# murdock_conn_v2.net
KiCad netlist of a schematic drawn in EAGLE
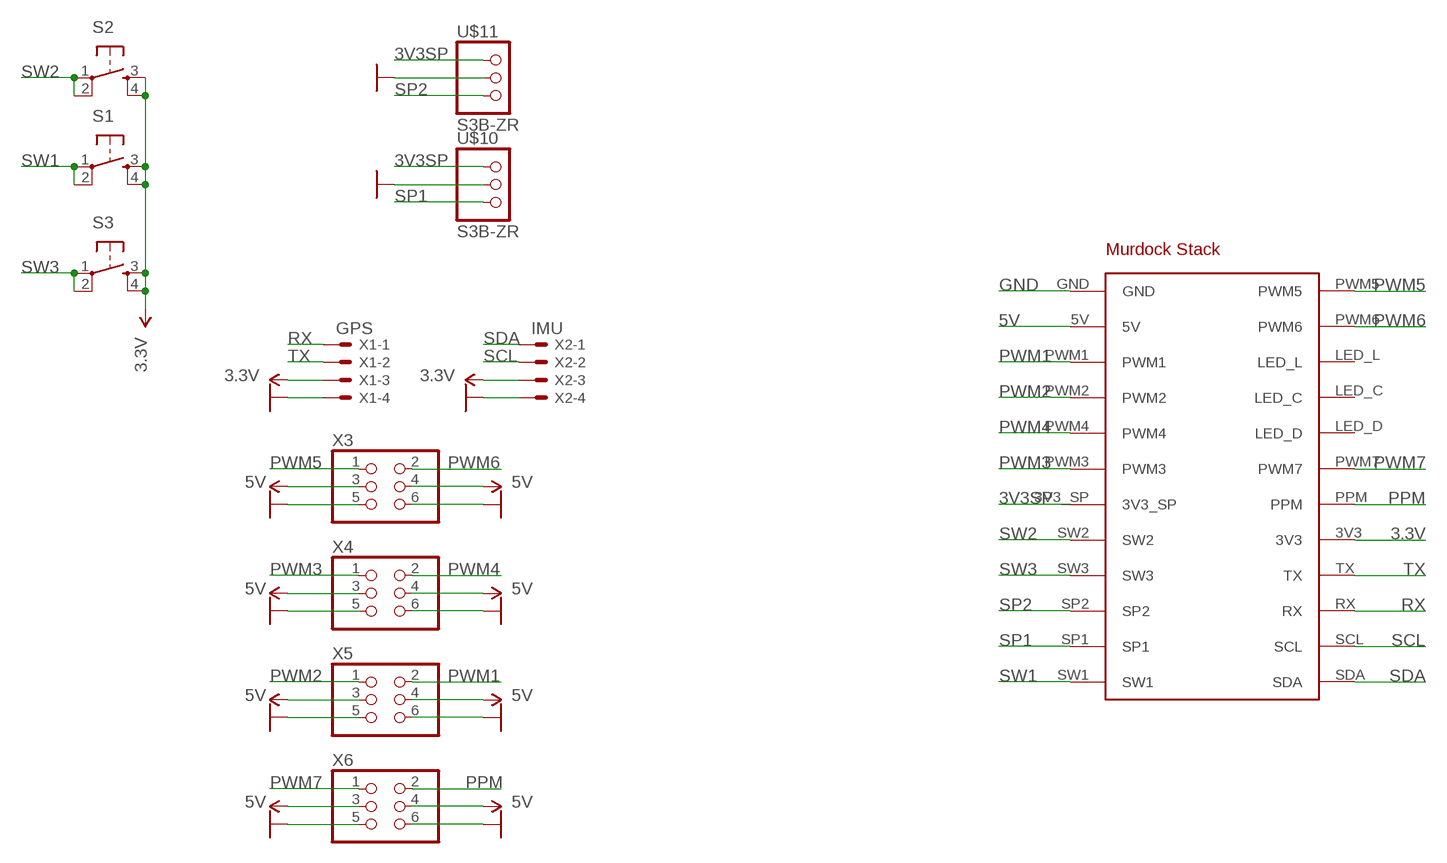
[diagram p0: schematic, sheet 1]

(export (version "E")
  (design (tool "Eeschema 10.0.6"))
  (components
    (comp (ref "S1")
      (value "LSH")
      (footprint "eagle-import:LSH")
      (libsource (lib "eagle-import") (part "LSH"))
    )
    (comp (ref "S2")
      (value "LSH")
      (footprint "eagle-import:LSH")
      (libsource (lib "eagle-import") (part "LSH"))
    )
    (comp (ref "S3")
      (value "LSH")
      (footprint "eagle-import:LSH")
      (libsource (lib "eagle-import") (part "LSH"))
    )
    (comp (ref "U$10")
      (value "S3B-ZR")
      (footprint "eagle-import:S3B-ZR")
      (libsource (lib "eagle-import") (part "S3B-ZR"))
    )
    (comp (ref "U$11")
      (value "S3B-ZR")
      (footprint "eagle-import:S3B-ZR")
      (libsource (lib "eagle-import") (part "S3B-ZR"))
    )
    (comp (ref "X1")
      (value "GPS")
      (footprint "eagle-import:70553-04")
      (libsource (lib "eagle-import") (part "C-GRID-04-70553"))
    )
    (comp (ref "X2")
      (value "IMU")
      (footprint "eagle-import:70553-04")
      (libsource (lib "eagle-import") (part "C-GRID-04-70553"))
    )
    (comp (ref "X3")
      (value "PINHD-2X3/90")
      (footprint "eagle-import:2X03_90")
      (libsource (lib "eagle-import") (part "PINHD-2X3/90"))
    )
    (comp (ref "X4")
      (value "PINHD-2X3/90")
      (footprint "eagle-import:2X03_90")
      (libsource (lib "eagle-import") (part "PINHD-2X3/90"))
    )
    (comp (ref "X5")
      (value "PINHD-2X3/90")
      (footprint "eagle-import:2X03_90")
      (libsource (lib "eagle-import") (part "PINHD-2X3/90"))
    )
    (comp (ref "X6")
      (value "PINHD-2X3/90")
      (footprint "eagle-import:2X03_90")
      (libsource (lib "eagle-import") (part "PINHD-2X3/90"))
    )
    (comp (ref "X7")
      (value "MURDOCK_STACK")
      (footprint "eagle-import:MURDOCK_STACK")
      (libsource (lib "eagle-import") (part "MURDOCK_STACK"))
    )
  )
  (nets
    (net (code "1") (name "/3V3SP") (class "Default")
      (node (ref "U$10") (pin "1") (pinfunction "1_1") (pintype "bidirectional"))
      (node (ref "U$11") (pin "1") (pinfunction "1_1") (pintype "bidirectional"))
      (node (ref "X7") (pin "3V3_SP") (pinfunction "3V3_SP_3V3_SP") (pintype "bidirectional"))
    )
    (net (code "2") (name "/PPM") (class "Default")
      (node (ref "X6") (pin "2") (pinfunction "2_2") (pintype "passive"))
      (node (ref "X7") (pin "PPM") (pinfunction "PPM_PPM") (pintype "bidirectional"))
    )
    (net (code "3") (name "/PWM1") (class "Default")
      (node (ref "X5") (pin "2") (pinfunction "2_2") (pintype "passive"))
      (node (ref "X7") (pin "PWM1") (pinfunction "PWM1_PWM1") (pintype "bidirectional"))
    )
    (net (code "4") (name "/PWM2") (class "Default")
      (node (ref "X5") (pin "1") (pinfunction "1_1") (pintype "passive"))
      (node (ref "X7") (pin "PWM2") (pinfunction "PWM2_PWM2") (pintype "bidirectional"))
    )
    (net (code "5") (name "/PWM3") (class "Default")
      (node (ref "X4") (pin "1") (pinfunction "1_1") (pintype "passive"))
      (node (ref "X7") (pin "PWM3") (pinfunction "PWM3_PWM3") (pintype "bidirectional"))
    )
    (net (code "6") (name "/PWM4") (class "Default")
      (node (ref "X4") (pin "2") (pinfunction "2_2") (pintype "passive"))
      (node (ref "X7") (pin "PWM4") (pinfunction "PWM4_PWM4") (pintype "bidirectional"))
    )
    (net (code "7") (name "/PWM5") (class "Default")
      (node (ref "X3") (pin "1") (pinfunction "1_1") (pintype "passive"))
      (node (ref "X7") (pin "PWM5") (pinfunction "PWM5_PWM5") (pintype "bidirectional"))
    )
    (net (code "8") (name "/PWM6") (class "Default")
      (node (ref "X3") (pin "2") (pinfunction "2_2") (pintype "passive"))
      (node (ref "X7") (pin "PWM6") (pinfunction "PWM6_PWM6") (pintype "bidirectional"))
    )
    (net (code "9") (name "/PWM7") (class "Default")
      (node (ref "X6") (pin "1") (pinfunction "1_1") (pintype "passive"))
      (node (ref "X7") (pin "PWM7") (pinfunction "PWM7_PWM7") (pintype "bidirectional"))
    )
    (net (code "10") (name "/RX") (class "Default")
      (node (ref "X1") (pin "1") (pinfunction "S_1") (pintype "passive"))
      (node (ref "X7") (pin "RX") (pinfunction "RX_RX") (pintype "bidirectional"))
    )
    (net (code "11") (name "/SCL") (class "Default")
      (node (ref "X2") (pin "2") (pinfunction "S_2") (pintype "passive"))
      (node (ref "X7") (pin "SCL") (pinfunction "SCL_SCL") (pintype "bidirectional"))
    )
    (net (code "12") (name "/SDA") (class "Default")
      (node (ref "X2") (pin "1") (pinfunction "S_1") (pintype "passive"))
      (node (ref "X7") (pin "SDA") (pinfunction "SDA_SDA") (pintype "bidirectional"))
    )
    (net (code "13") (name "/SP1") (class "Default")
      (node (ref "U$10") (pin "3") (pinfunction "3_3") (pintype "bidirectional"))
      (node (ref "X7") (pin "SP1") (pinfunction "SP1_SP1") (pintype "bidirectional"))
    )
    (net (code "14") (name "/SP2") (class "Default")
      (node (ref "U$11") (pin "3") (pinfunction "3_3") (pintype "bidirectional"))
      (node (ref "X7") (pin "SP2") (pinfunction "SP2_SP2") (pintype "bidirectional"))
    )
    (net (code "15") (name "/SW1") (class "Default")
      (node (ref "S1") (pin "1") (pinfunction "1_1") (pintype "passive"))
      (node (ref "S1") (pin "2") (pinfunction "2_2") (pintype "passive"))
      (node (ref "X7") (pin "SW1") (pinfunction "SW1_SW1") (pintype "bidirectional"))
    )
    (net (code "16") (name "/SW2") (class "Default")
      (node (ref "S2") (pin "1") (pinfunction "1_1") (pintype "passive"))
      (node (ref "S2") (pin "2") (pinfunction "2_2") (pintype "passive"))
      (node (ref "X7") (pin "SW2") (pinfunction "SW2_SW2") (pintype "bidirectional"))
    )
    (net (code "17") (name "/SW3") (class "Default")
      (node (ref "S3") (pin "1") (pinfunction "1_1") (pintype "passive"))
      (node (ref "S3") (pin "2") (pinfunction "2_2") (pintype "passive"))
      (node (ref "X7") (pin "SW3") (pinfunction "SW3_SW3") (pintype "bidirectional"))
    )
    (net (code "18") (name "/TX") (class "Default")
      (node (ref "X1") (pin "2") (pinfunction "S_2") (pintype "passive"))
      (node (ref "X7") (pin "TX") (pinfunction "TX_TX") (pintype "bidirectional"))
    )
    (net (code "19") (name "3.3V") (class "Default")
      (node (ref "S1") (pin "3") (pinfunction "3_3") (pintype "passive"))
      (node (ref "S1") (pin "4") (pinfunction "4_4") (pintype "passive"))
      (node (ref "S2") (pin "3") (pinfunction "3_3") (pintype "passive"))
      (node (ref "S2") (pin "4") (pinfunction "4_4") (pintype "passive"))
      (node (ref "S3") (pin "3") (pinfunction "3_3") (pintype "passive"))
      (node (ref "S3") (pin "4") (pinfunction "4_4") (pintype "passive"))
      (node (ref "X1") (pin "3") (pinfunction "S_3") (pintype "passive"))
      (node (ref "X2") (pin "3") (pinfunction "S_3") (pintype "passive"))
      (node (ref "X7") (pin "3V3") (pinfunction "3V3_3V3") (pintype "bidirectional"))
    )
    (net (code "20") (name "5V") (class "Default")
      (node (ref "X3") (pin "3") (pinfunction "3_3") (pintype "passive"))
      (node (ref "X3") (pin "4") (pinfunction "4_4") (pintype "passive"))
      (node (ref "X4") (pin "3") (pinfunction "3_3") (pintype "passive"))
      (node (ref "X4") (pin "4") (pinfunction "4_4") (pintype "passive"))
      (node (ref "X5") (pin "3") (pinfunction "3_3") (pintype "passive"))
      (node (ref "X5") (pin "4") (pinfunction "4_4") (pintype "passive"))
      (node (ref "X6") (pin "3") (pinfunction "3_3") (pintype "passive"))
      (node (ref "X6") (pin "4") (pinfunction "4_4") (pintype "passive"))
      (node (ref "X7") (pin "5V") (pinfunction "5V_5V") (pintype "bidirectional"))
    )
    (net (code "21") (name "GND") (class "Default")
      (node (ref "U$10") (pin "2") (pinfunction "2_2") (pintype "bidirectional"))
      (node (ref "U$11") (pin "2") (pinfunction "2_2") (pintype "bidirectional"))
      (node (ref "X1") (pin "4") (pinfunction "S_4") (pintype "passive"))
      (node (ref "X2") (pin "4") (pinfunction "S_4") (pintype "passive"))
      (node (ref "X3") (pin "5") (pinfunction "5_5") (pintype "passive"))
      (node (ref "X3") (pin "6") (pinfunction "6_6") (pintype "passive"))
      (node (ref "X4") (pin "5") (pinfunction "5_5") (pintype "passive"))
      (node (ref "X4") (pin "6") (pinfunction "6_6") (pintype "passive"))
      (node (ref "X5") (pin "5") (pinfunction "5_5") (pintype "passive"))
      (node (ref "X5") (pin "6") (pinfunction "6_6") (pintype "passive"))
      (node (ref "X6") (pin "5") (pinfunction "5_5") (pintype "passive"))
      (node (ref "X6") (pin "6") (pinfunction "6_6") (pintype "passive"))
      (node (ref "X7") (pin "GND") (pinfunction "GND_GND") (pintype "bidirectional"))
    )
    (net (code "22") (name "unconnected-(X7-PadLED_C)") (class "Default")
      (node (ref "X7") (pin "LED_C") (pinfunction "LED_C_LED_C") (pintype "bidirectional"))
    )
    (net (code "23") (name "unconnected-(X7-PadLED_D)") (class "Default")
      (node (ref "X7") (pin "LED_D") (pinfunction "LED_D_LED_D") (pintype "bidirectional"))
    )
    (net (code "24") (name "unconnected-(X7-PadLED_L)") (class "Default")
      (node (ref "X7") (pin "LED_L") (pinfunction "LED_L_LED_L") (pintype "bidirectional"))
    )
  )
)
